# micro_board.net
KiCad netlist of a schematic drawn in EAGLE
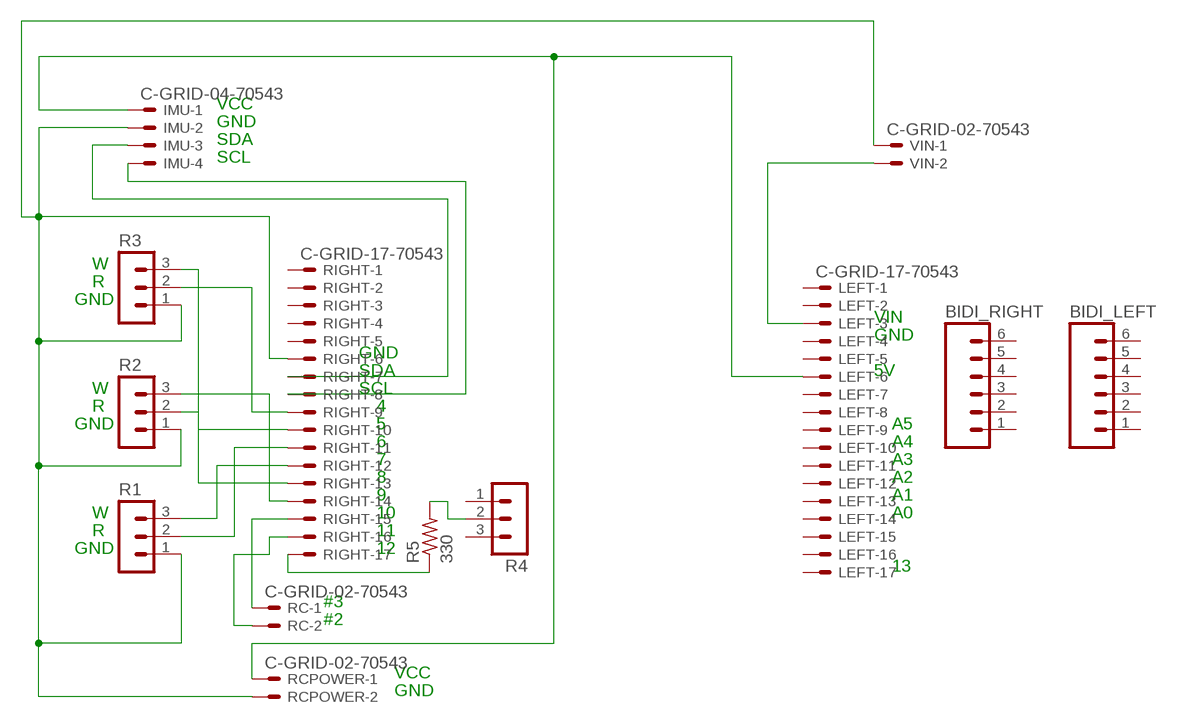
[diagram p0: schematic, sheet 1]

(export (version "E")
  (design (tool "Eeschema 10.0.6"))
  (components
    (comp (ref "BIDI_LEFT")
      (value "M06LONGPADS")
      (footprint "eagle-import:1X06_LONGPADS")
      (libsource (lib "eagle-import") (part "M06LONGPADS"))
    )
    (comp (ref "BIDI_RIGHT")
      (value "M06LONGPADS")
      (footprint "eagle-import:1X06_LONGPADS")
      (libsource (lib "eagle-import") (part "M06LONGPADS"))
    )
    (comp (ref "IMU")
      (value "C-GRID-04-70543")
      (footprint "eagle-import:70543-04")
      (libsource (lib "eagle-import") (part "C-GRID-04-70543"))
    )
    (comp (ref "LEFT")
      (value "C-GRID-17-70543")
      (footprint "eagle-import:70543-17")
      (libsource (lib "eagle-import") (part "C-GRID-17-70543"))
    )
    (comp (ref "R1")
      (value "MA03-1")
      (footprint "eagle-import:MA03-1")
      (fields (field (name "OC_FARNELL") "unknown") (field (name "OC_NEWARK") "unknown"))
      (libsource (lib "eagle-import") (part "MA03-1"))
    )
    (comp (ref "R2")
      (value "MA03-1")
      (footprint "eagle-import:MA03-1")
      (libsource (lib "eagle-import") (part "MA03-1"))
    )
    (comp (ref "R3")
      (value "MA03-1")
      (footprint "eagle-import:MA03-1")
      (fields (field (name "OC_FARNELL") "unknown") (field (name "OC_NEWARK") "unknown"))
      (libsource (lib "eagle-import") (part "MA03-1"))
    )
    (comp (ref "R4")
      (value "MA03-1")
      (footprint "eagle-import:MA03-1")
      (fields (field (name "OC_FARNELL") "unknown") (field (name "OC_NEWARK") "unknown"))
      (libsource (lib "eagle-import") (part "MA03-1"))
    )
    (comp (ref "R5")
      (value "330")
      (footprint "eagle-import:0207_12")
      (libsource (lib "eagle-import") (part "R-US_0207/12"))
    )
    (comp (ref "RC")
      (value "C-GRID-02-70543")
      (footprint "eagle-import:70543-02")
      (libsource (lib "eagle-import") (part "C-GRID-02-70543"))
    )
    (comp (ref "RCPOWER")
      (value "C-GRID-02-70543")
      (footprint "eagle-import:70543-02")
      (libsource (lib "eagle-import") (part "C-GRID-02-70543"))
    )
    (comp (ref "RIGHT")
      (value "C-GRID-17-70543")
      (footprint "eagle-import:70543-17")
      (libsource (lib "eagle-import") (part "C-GRID-17-70543"))
    )
    (comp (ref "VIN")
      (value "C-GRID-02-70543")
      (footprint "eagle-import:70543-02")
      (fields (field (name "OC_FARNELL") "unknown") (field (name "OC_NEWARK") "unknown"))
      (libsource (lib "eagle-import") (part "C-GRID-02-70543"))
    )
  )
  (nets
    (net (code "1") (name "Net-(IMUA-S)") (class "Default")
      (node (ref "IMU") (pin "1") (pinfunction "S_1") (pintype "passive"))
      (node (ref "LEFT") (pin "6") (pinfunction "S_6") (pintype "passive"))
      (node (ref "RCPOWER") (pin "1") (pinfunction "S_1") (pintype "passive"))
    )
    (net (code "2") (name "Net-(IMUB-S)") (class "Default")
      (node (ref "IMU") (pin "2") (pinfunction "S_2") (pintype "passive"))
      (node (ref "R1") (pin "1") (pinfunction "1_1") (pintype "passive"))
      (node (ref "R2") (pin "1") (pinfunction "1_1") (pintype "passive"))
      (node (ref "R3") (pin "1") (pinfunction "1_1") (pintype "passive"))
      (node (ref "RCPOWER") (pin "2") (pinfunction "S_2") (pintype "passive"))
      (node (ref "RIGHT") (pin "6") (pinfunction "S_6") (pintype "passive"))
      (node (ref "VIN") (pin "1") (pinfunction "S_1") (pintype "passive"))
    )
    (net (code "3") (name "Net-(IMUC-S)") (class "Default")
      (node (ref "IMU") (pin "3") (pinfunction "S_3") (pintype "passive"))
      (node (ref "RIGHT") (pin "7") (pinfunction "S_7") (pintype "passive"))
    )
    (net (code "4") (name "Net-(IMUD-S)") (class "Default")
      (node (ref "IMU") (pin "4") (pinfunction "S_4") (pintype "passive"))
      (node (ref "RIGHT") (pin "8") (pinfunction "S_8") (pintype "passive"))
    )
    (net (code "5") (name "Net-(LEFTK-S)") (class "Default")
      (node (ref "LEFT") (pin "3") (pinfunction "S_3") (pintype "passive"))
      (node (ref "VIN") (pin "2") (pinfunction "S_2") (pintype "passive"))
    )
    (net (code "6") (name "Net-(R4-Pad2)") (class "Default")
      (node (ref "R4") (pin "2") (pinfunction "2_2") (pintype "passive"))
      (node (ref "R5") (pin "2") (pinfunction "2_2") (pintype "passive"))
    )
    (net (code "7") (name "Net-(RCA-S)") (class "Default")
      (node (ref "RC") (pin "1") (pinfunction "S_1") (pintype "passive"))
      (node (ref "RIGHT") (pin "15") (pinfunction "S_15") (pintype "passive"))
    )
    (net (code "8") (name "Net-(RCB-S)") (class "Default")
      (node (ref "RC") (pin "2") (pinfunction "S_2") (pintype "passive"))
      (node (ref "RIGHT") (pin "16") (pinfunction "S_16") (pintype "passive"))
    )
    (net (code "9") (name "Net-(RIGHTB-S)") (class "Default")
      (node (ref "R2") (pin "2") (pinfunction "2_2") (pintype "passive"))
      (node (ref "RIGHT") (pin "10") (pinfunction "S_10") (pintype "passive"))
    )
    (net (code "10") (name "Net-(RIGHTC-S)") (class "Default")
      (node (ref "R1") (pin "2") (pinfunction "2_2") (pintype "passive"))
      (node (ref "RIGHT") (pin "11") (pinfunction "S_11") (pintype "passive"))
    )
    (net (code "11") (name "Net-(RIGHTD-S)") (class "Default")
      (node (ref "R1") (pin "3") (pinfunction "3_3") (pintype "passive"))
      (node (ref "RIGHT") (pin "12") (pinfunction "S_12") (pintype "passive"))
    )
    (net (code "12") (name "Net-(RIGHTE-S)") (class "Default")
      (node (ref "R3") (pin "3") (pinfunction "3_3") (pintype "passive"))
      (node (ref "RIGHT") (pin "13") (pinfunction "S_13") (pintype "passive"))
    )
    (net (code "13") (name "Net-(RIGHTF-S)") (class "Default")
      (node (ref "R2") (pin "3") (pinfunction "3_3") (pintype "passive"))
      (node (ref "RIGHT") (pin "14") (pinfunction "S_14") (pintype "passive"))
    )
    (net (code "14") (name "Net-(RIGHTI-S)") (class "Default")
      (node (ref "R5") (pin "1") (pinfunction "1_1") (pintype "passive"))
      (node (ref "RIGHT") (pin "17") (pinfunction "S_17") (pintype "passive"))
    )
    (net (code "15") (name "Net-(RIGHTQ-S)") (class "Default")
      (node (ref "R3") (pin "2") (pinfunction "2_2") (pintype "passive"))
      (node (ref "RIGHT") (pin "9") (pinfunction "S_9") (pintype "passive"))
    )
    (net (code "16") (name "unconnected-(BIDI_LEFT-Pad1)") (class "Default")
      (node (ref "BIDI_LEFT") (pin "1") (pinfunction "1_1") (pintype "passive"))
    )
    (net (code "17") (name "unconnected-(BIDI_LEFT-Pad2)") (class "Default")
      (node (ref "BIDI_LEFT") (pin "2") (pinfunction "2_2") (pintype "passive"))
    )
    (net (code "18") (name "unconnected-(BIDI_LEFT-Pad3)") (class "Default")
      (node (ref "BIDI_LEFT") (pin "3") (pinfunction "3_3") (pintype "passive"))
    )
    (net (code "19") (name "unconnected-(BIDI_LEFT-Pad4)") (class "Default")
      (node (ref "BIDI_LEFT") (pin "4") (pinfunction "4_4") (pintype "passive"))
    )
    (net (code "20") (name "unconnected-(BIDI_LEFT-Pad5)") (class "Default")
      (node (ref "BIDI_LEFT") (pin "5") (pinfunction "5_5") (pintype "passive"))
    )
    (net (code "21") (name "unconnected-(BIDI_LEFT-Pad6)") (class "Default")
      (node (ref "BIDI_LEFT") (pin "6") (pinfunction "6_6") (pintype "passive"))
    )
    (net (code "22") (name "unconnected-(BIDI_RIGHT-Pad1)") (class "Default")
      (node (ref "BIDI_RIGHT") (pin "1") (pinfunction "1_1") (pintype "passive"))
    )
    (net (code "23") (name "unconnected-(BIDI_RIGHT-Pad2)") (class "Default")
      (node (ref "BIDI_RIGHT") (pin "2") (pinfunction "2_2") (pintype "passive"))
    )
    (net (code "24") (name "unconnected-(BIDI_RIGHT-Pad3)") (class "Default")
      (node (ref "BIDI_RIGHT") (pin "3") (pinfunction "3_3") (pintype "passive"))
    )
    (net (code "25") (name "unconnected-(BIDI_RIGHT-Pad4)") (class "Default")
      (node (ref "BIDI_RIGHT") (pin "4") (pinfunction "4_4") (pintype "passive"))
    )
    (net (code "26") (name "unconnected-(BIDI_RIGHT-Pad5)") (class "Default")
      (node (ref "BIDI_RIGHT") (pin "5") (pinfunction "5_5") (pintype "passive"))
    )
    (net (code "27") (name "unconnected-(BIDI_RIGHT-Pad6)") (class "Default")
      (node (ref "BIDI_RIGHT") (pin "6") (pinfunction "6_6") (pintype "passive"))
    )
    (net (code "28") (name "unconnected-(LEFTA-S-Pad1)") (class "Default")
      (node (ref "LEFT") (pin "1") (pinfunction "S_1") (pintype "passive"))
    )
    (net (code "29") (name "unconnected-(LEFTB-S-Pad10)") (class "Default")
      (node (ref "LEFT") (pin "10") (pinfunction "S_10") (pintype "passive"))
    )
    (net (code "30") (name "unconnected-(LEFTC-S-Pad11)") (class "Default")
      (node (ref "LEFT") (pin "11") (pinfunction "S_11") (pintype "passive"))
    )
    (net (code "31") (name "unconnected-(LEFTD-S-Pad12)") (class "Default")
      (node (ref "LEFT") (pin "12") (pinfunction "S_12") (pintype "passive"))
    )
    (net (code "32") (name "unconnected-(LEFTE-S-Pad13)") (class "Default")
      (node (ref "LEFT") (pin "13") (pinfunction "S_13") (pintype "passive"))
    )
    (net (code "33") (name "unconnected-(LEFTF-S-Pad14)") (class "Default")
      (node (ref "LEFT") (pin "14") (pinfunction "S_14") (pintype "passive"))
    )
    (net (code "34") (name "unconnected-(LEFTG-S-Pad15)") (class "Default")
      (node (ref "LEFT") (pin "15") (pinfunction "S_15") (pintype "passive"))
    )
    (net (code "35") (name "unconnected-(LEFTH-S-Pad16)") (class "Default")
      (node (ref "LEFT") (pin "16") (pinfunction "S_16") (pintype "passive"))
    )
    (net (code "36") (name "unconnected-(LEFTI-S-Pad17)") (class "Default")
      (node (ref "LEFT") (pin "17") (pinfunction "S_17") (pintype "passive"))
    )
    (net (code "37") (name "unconnected-(LEFTJ-S-Pad2)") (class "Default")
      (node (ref "LEFT") (pin "2") (pinfunction "S_2") (pintype "passive"))
    )
    (net (code "38") (name "unconnected-(LEFTL-S-Pad4)") (class "Default")
      (node (ref "LEFT") (pin "4") (pinfunction "S_4") (pintype "passive"))
    )
    (net (code "39") (name "unconnected-(LEFTM-S-Pad5)") (class "Default")
      (node (ref "LEFT") (pin "5") (pinfunction "S_5") (pintype "passive"))
    )
    (net (code "40") (name "unconnected-(LEFTO-S-Pad7)") (class "Default")
      (node (ref "LEFT") (pin "7") (pinfunction "S_7") (pintype "passive"))
    )
    (net (code "41") (name "unconnected-(LEFTP-S-Pad8)") (class "Default")
      (node (ref "LEFT") (pin "8") (pinfunction "S_8") (pintype "passive"))
    )
    (net (code "42") (name "unconnected-(LEFTQ-S-Pad9)") (class "Default")
      (node (ref "LEFT") (pin "9") (pinfunction "S_9") (pintype "passive"))
    )
    (net (code "43") (name "unconnected-(R4-Pad1)") (class "Default")
      (node (ref "R4") (pin "1") (pinfunction "1_1") (pintype "passive"))
    )
    (net (code "44") (name "unconnected-(R4-Pad3)") (class "Default")
      (node (ref "R4") (pin "3") (pinfunction "3_3") (pintype "passive"))
    )
    (net (code "45") (name "unconnected-(RIGHTA-S-Pad1)") (class "Default")
      (node (ref "RIGHT") (pin "1") (pinfunction "S_1") (pintype "passive"))
    )
    (net (code "46") (name "unconnected-(RIGHTJ-S-Pad2)") (class "Default")
      (node (ref "RIGHT") (pin "2") (pinfunction "S_2") (pintype "passive"))
    )
    (net (code "47") (name "unconnected-(RIGHTK-S-Pad3)") (class "Default")
      (node (ref "RIGHT") (pin "3") (pinfunction "S_3") (pintype "passive"))
    )
    (net (code "48") (name "unconnected-(RIGHTL-S-Pad4)") (class "Default")
      (node (ref "RIGHT") (pin "4") (pinfunction "S_4") (pintype "passive"))
    )
    (net (code "49") (name "unconnected-(RIGHTM-S-Pad5)") (class "Default")
      (node (ref "RIGHT") (pin "5") (pinfunction "S_5") (pintype "passive"))
    )
  )
)
